# 9xVoice_MikeB_TH_v1_0a.net
KiCad netlist of a schematic drawn in EAGLE
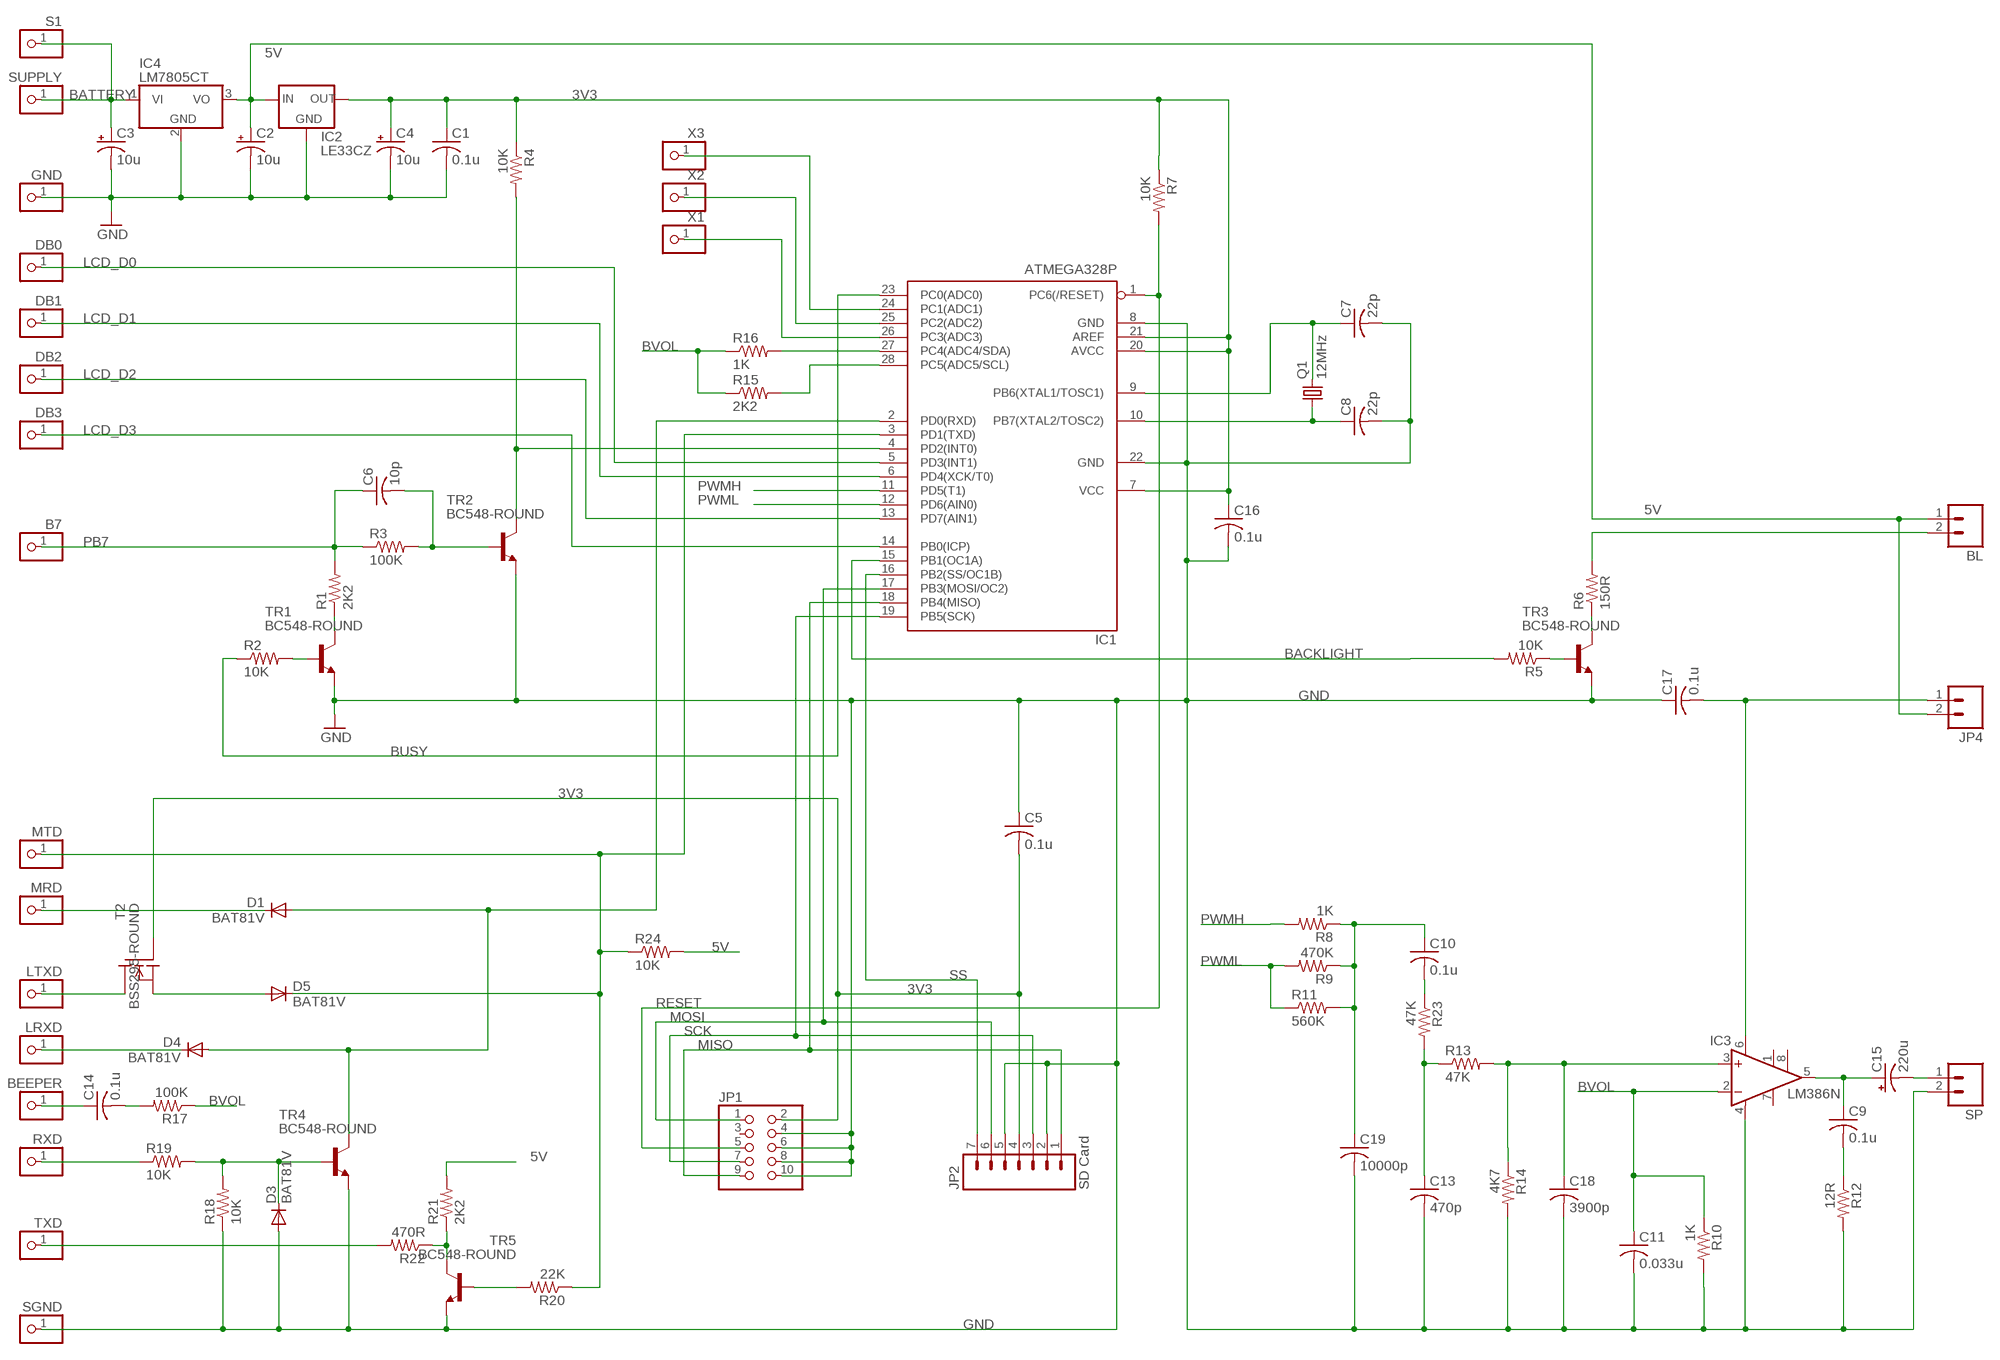
[diagram p0: schematic, sheet 1]

(export (version "E")
  (design (tool "Eeschema 10.0.6"))
  (components
    (comp (ref "B7")
      (value "PINHD-1X1")
      (footprint "eagle-import:1X01")
      (libsource (lib "eagle-import") (part "PINHD-1X1"))
    )
    (comp (ref "BEEPER")
      (value "PINHD-1X1")
      (footprint "eagle-import:1X01")
      (libsource (lib "eagle-import") (part "PINHD-1X1"))
    )
    (comp (ref "BL")
      (value "M02PTH")
      (footprint "eagle-import:1X02")
      (libsource (lib "eagle-import") (part "M02PTH"))
    )
    (comp (ref "C1")
      (value "0.1u")
      (footprint "eagle-import:C025-024X044")
      (libsource (lib "eagle-import") (part "C-US025-024X044"))
    )
    (comp (ref "C2")
      (value "10u")
      (footprint "eagle-import:E2,5-5")
      (libsource (lib "eagle-import") (part "CPOL-USE2.5-5"))
    )
    (comp (ref "C3")
      (value "10u")
      (footprint "eagle-import:E2,5-5")
      (libsource (lib "eagle-import") (part "CPOL-USE2.5-5"))
    )
    (comp (ref "C4")
      (value "10u")
      (footprint "eagle-import:E2,5-5")
      (libsource (lib "eagle-import") (part "CPOL-USE2.5-5"))
    )
    (comp (ref "C5")
      (value "0.1u")
      (footprint "eagle-import:C025-024X044")
      (libsource (lib "eagle-import") (part "C-US025-024X044"))
    )
    (comp (ref "C6")
      (value "10p")
      (footprint "eagle-import:C025-024X044")
      (libsource (lib "eagle-import") (part "C-US025-024X044"))
    )
    (comp (ref "C7")
      (value "22p")
      (footprint "eagle-import:C025-024X044")
      (libsource (lib "eagle-import") (part "C-US025-024X044"))
    )
    (comp (ref "C8")
      (value "22p")
      (footprint "eagle-import:C025-024X044")
      (libsource (lib "eagle-import") (part "C-US025-024X044"))
    )
    (comp (ref "C9")
      (value "0.1u")
      (footprint "eagle-import:C025-024X044")
      (libsource (lib "eagle-import") (part "C-US025-024X044"))
    )
    (comp (ref "C10")
      (value "0.1u")
      (footprint "eagle-import:C025-024X044")
      (libsource (lib "eagle-import") (part "C-US025-024X044"))
    )
    (comp (ref "C11")
      (value "0.033u")
      (footprint "eagle-import:C025-024X044")
      (libsource (lib "eagle-import") (part "C-US025-024X044"))
    )
    (comp (ref "C13")
      (value "470p")
      (footprint "eagle-import:C025-024X044")
      (libsource (lib "eagle-import") (part "C-US025-024X044"))
    )
    (comp (ref "C14")
      (value "0.1u")
      (footprint "eagle-import:C025-024X044")
      (libsource (lib "eagle-import") (part "C-US025-024X044"))
    )
    (comp (ref "C15")
      (value "220u")
      (footprint "eagle-import:E5-8,5")
      (libsource (lib "eagle-import") (part "CPOL-USE5-8.5"))
    )
    (comp (ref "C16")
      (value "0.1u")
      (footprint "eagle-import:C025-024X044")
      (libsource (lib "eagle-import") (part "C-US025-024X044"))
    )
    (comp (ref "C17")
      (value "0.1u")
      (footprint "eagle-import:C025-024X044")
      (libsource (lib "eagle-import") (part "C-US025-024X044"))
    )
    (comp (ref "C18")
      (value "3900p")
      (footprint "eagle-import:C025-024X044")
      (libsource (lib "eagle-import") (part "C-US025-024X044"))
    )
    (comp (ref "C19")
      (value "10000p")
      (footprint "eagle-import:C025-024X044")
      (libsource (lib "eagle-import") (part "C-US025-024X044"))
    )
    (comp (ref "D1")
      (value "BAT81V")
      (footprint "eagle-import:D-2.5")
      (libsource (lib "eagle-import") (part "DIODE-D-2.5"))
    )
    (comp (ref "D3")
      (value "BAT81V")
      (footprint "eagle-import:D-2.5")
      (libsource (lib "eagle-import") (part "DIODE-D-2.5"))
    )
    (comp (ref "D4")
      (value "BAT81V")
      (footprint "eagle-import:D-2.5")
      (libsource (lib "eagle-import") (part "DIODE-D-2.5"))
    )
    (comp (ref "D5")
      (value "BAT81V")
      (footprint "eagle-import:D-2.5")
      (libsource (lib "eagle-import") (part "DIODE-D-2.5"))
    )
    (comp (ref "DB0")
      (value "PINHD-1X1")
      (footprint "eagle-import:1X01")
      (libsource (lib "eagle-import") (part "PINHD-1X1"))
    )
    (comp (ref "DB1")
      (value "PINHD-1X1")
      (footprint "eagle-import:1X01")
      (libsource (lib "eagle-import") (part "PINHD-1X1"))
    )
    (comp (ref "DB2")
      (value "PINHD-1X1")
      (footprint "eagle-import:1X01")
      (libsource (lib "eagle-import") (part "PINHD-1X1"))
    )
    (comp (ref "DB3")
      (value "PINHD-1X1")
      (footprint "eagle-import:1X01")
      (libsource (lib "eagle-import") (part "PINHD-1X1"))
    )
    (comp (ref "GND")
      (value "PINHD-1X1")
      (footprint "eagle-import:1X01")
      (libsource (lib "eagle-import") (part "PINHD-1X1"))
    )
    (comp (ref "IC1")
      (value "ATMEGA328P")
      (footprint "eagle-import:DIL28-3-JDC")
      (libsource (lib "eagle-import") (part "MEGA8-P-JDCJDC"))
    )
    (comp (ref "IC2")
      (value "LE33CZ")
      (footprint "eagle-import:TO92-JDC")
      (libsource (lib "eagle-import") (part "78LXX-ROUND"))
    )
    (comp (ref "IC3")
      (value "LM386N")
      (footprint "eagle-import:DIL08")
      (libsource (lib "eagle-import") (part "LM386?-N1"))
    )
    (comp (ref "IC4")
      (value "LM7805CT")
      (footprint "eagle-import:TO220H")
      (libsource (lib "eagle-import") (part "78T05"))
    )
    (comp (ref "JP1")
      (value "PINHD-2X5")
      (footprint "eagle-import:2X05")
      (libsource (lib "eagle-import") (part "PINHD-2X5"))
    )
    (comp (ref "JP2")
      (value "SD Card")
      (footprint "eagle-import:1X07")
      (libsource (lib "eagle-import") (part "M07"))
    )
    (comp (ref "JP4")
      (value "M02PTH")
      (footprint "eagle-import:1X02")
      (libsource (lib "eagle-import") (part "M02PTH"))
    )
    (comp (ref "LRXD")
      (value "PINHD-1X1")
      (footprint "eagle-import:1X01")
      (libsource (lib "eagle-import") (part "PINHD-1X1"))
    )
    (comp (ref "LTXD")
      (value "PINHD-1X1")
      (footprint "eagle-import:1X01")
      (libsource (lib "eagle-import") (part "PINHD-1X1"))
    )
    (comp (ref "MRD")
      (value "PINHD-1X1")
      (footprint "eagle-import:1X01")
      (libsource (lib "eagle-import") (part "PINHD-1X1"))
    )
    (comp (ref "MTD")
      (value "PINHD-1X1")
      (footprint "eagle-import:1X01")
      (libsource (lib "eagle-import") (part "PINHD-1X1"))
    )
    (comp (ref "Q1")
      (value "12MHz")
      (footprint "eagle-import:HC49US")
      (libsource (lib "eagle-import") (part "CRYSTALHC49US"))
    )
    (comp (ref "R1")
      (value "2K2")
      (footprint "eagle-import:0207_2V")
      (libsource (lib "eagle-import") (part "R-US_0207/2V"))
    )
    (comp (ref "R2")
      (value "10K")
      (footprint "eagle-import:0204_7")
      (libsource (lib "eagle-import") (part "R-US_0204/7"))
    )
    (comp (ref "R3")
      (value "100K")
      (footprint "eagle-import:0207_2V")
      (libsource (lib "eagle-import") (part "R-US_0207/2V"))
    )
    (comp (ref "R4")
      (value "10K")
      (footprint "eagle-import:0207_2V")
      (libsource (lib "eagle-import") (part "R-US_0207/2V"))
    )
    (comp (ref "R5")
      (value "10K")
      (footprint "eagle-import:0207_2V")
      (libsource (lib "eagle-import") (part "R-US_0207/2V"))
    )
    (comp (ref "R6")
      (value "150R")
      (footprint "eagle-import:0207_2V")
      (libsource (lib "eagle-import") (part "R-US_0207/2V"))
    )
    (comp (ref "R7")
      (value "10K")
      (footprint "eagle-import:0207_2V")
      (libsource (lib "eagle-import") (part "R-US_0207/2V"))
    )
    (comp (ref "R8")
      (value "1K")
      (footprint "eagle-import:0207_2V")
      (libsource (lib "eagle-import") (part "R-US_0207/2V"))
    )
    (comp (ref "R9")
      (value "470K")
      (footprint "eagle-import:0207_2V")
      (libsource (lib "eagle-import") (part "R-US_0207/2V"))
    )
    (comp (ref "R10")
      (value "1K")
      (footprint "eagle-import:0207_2V")
      (libsource (lib "eagle-import") (part "R-US_0207/2V"))
    )
    (comp (ref "R11")
      (value "560K")
      (footprint "eagle-import:0207_2V")
      (libsource (lib "eagle-import") (part "R-US_0207/2V"))
    )
    (comp (ref "R12")
      (value "12R")
      (footprint "eagle-import:0207_2V")
      (libsource (lib "eagle-import") (part "R-US_0207/2V"))
    )
    (comp (ref "R13")
      (value "47K")
      (footprint "eagle-import:0207_2V")
      (libsource (lib "eagle-import") (part "R-US_0207/2V"))
    )
    (comp (ref "R14")
      (value "4K7")
      (footprint "eagle-import:0207_2V")
      (libsource (lib "eagle-import") (part "R-US_0207/2V"))
    )
    (comp (ref "R15")
      (value "2K2")
      (footprint "eagle-import:0207_2V")
      (libsource (lib "eagle-import") (part "R-US_0207/2V"))
    )
    (comp (ref "R16")
      (value "1K")
      (footprint "eagle-import:0207_2V")
      (libsource (lib "eagle-import") (part "R-US_0207/2V"))
    )
    (comp (ref "R17")
      (value "100K")
      (footprint "eagle-import:0207_2V")
      (libsource (lib "eagle-import") (part "R-US_0207/2V"))
    )
    (comp (ref "R18")
      (value "10K")
      (footprint "eagle-import:0207_2V")
      (libsource (lib "eagle-import") (part "R-US_0207/2V"))
    )
    (comp (ref "R19")
      (value "10K")
      (footprint "eagle-import:0207_2V")
      (libsource (lib "eagle-import") (part "R-US_0207/2V"))
    )
    (comp (ref "R20")
      (value "22K")
      (footprint "eagle-import:0207_2V")
      (libsource (lib "eagle-import") (part "R-US_0207/2V"))
    )
    (comp (ref "R21")
      (value "2K2")
      (footprint "eagle-import:0207_2V")
      (libsource (lib "eagle-import") (part "R-US_0207/2V"))
    )
    (comp (ref "R22")
      (value "470R")
      (footprint "eagle-import:0207_2V")
      (libsource (lib "eagle-import") (part "R-US_0207/2V"))
    )
    (comp (ref "R23")
      (value "47K")
      (footprint "eagle-import:0207_2V")
      (libsource (lib "eagle-import") (part "R-US_0207/2V"))
    )
    (comp (ref "R24")
      (value "10K")
      (footprint "eagle-import:0207_2V")
      (libsource (lib "eagle-import") (part "R-US_0207/2V"))
    )
    (comp (ref "RXD")
      (value "PINHD-1X1")
      (footprint "eagle-import:1X01")
      (libsource (lib "eagle-import") (part "PINHD-1X1"))
    )
    (comp (ref "S1")
      (value "PINHD-1X1")
      (footprint "eagle-import:1X01")
      (libsource (lib "eagle-import") (part "PINHD-1X1"))
    )
    (comp (ref "SGND")
      (value "PINHD-1X1")
      (footprint "eagle-import:1X01")
      (libsource (lib "eagle-import") (part "PINHD-1X1"))
    )
    (comp (ref "SP")
      (value "M02PTH")
      (footprint "eagle-import:1X02")
      (libsource (lib "eagle-import") (part "M02PTH"))
    )
    (comp (ref "SUPPLY")
      (value "PINHD-1X1")
      (footprint "eagle-import:1X01")
      (libsource (lib "eagle-import") (part "PINHD-1X1"))
    )
    (comp (ref "T2")
      (value "BSS295-ROUND")
      (footprint "eagle-import:TO92-JDC")
      (libsource (lib "eagle-import") (part "BSS295-ROUND"))
    )
    (comp (ref "TR1")
      (value "BC548-ROUND")
      (footprint "eagle-import:TO92-JDC")
      (libsource (lib "eagle-import") (part "BC548-ROUND"))
    )
    (comp (ref "TR2")
      (value "BC548-ROUND")
      (footprint "eagle-import:TO92-JDC")
      (libsource (lib "eagle-import") (part "BC548-ROUND"))
    )
    (comp (ref "TR3")
      (value "BC548-ROUND")
      (footprint "eagle-import:TO92-JDC")
      (libsource (lib "eagle-import") (part "BC548-ROUND"))
    )
    (comp (ref "TR4")
      (value "BC548-ROUND")
      (footprint "eagle-import:TO92-JDC")
      (libsource (lib "eagle-import") (part "BC548-ROUND"))
    )
    (comp (ref "TR5")
      (value "BC548-ROUND")
      (footprint "eagle-import:TO92-JDC")
      (libsource (lib "eagle-import") (part "BC548-ROUND"))
    )
    (comp (ref "TXD")
      (value "PINHD-1X1")
      (footprint "eagle-import:1X01")
      (libsource (lib "eagle-import") (part "PINHD-1X1"))
    )
    (comp (ref "X1")
      (value "PINHD-1X1")
      (footprint "eagle-import:1X01")
      (libsource (lib "eagle-import") (part "PINHD-1X1"))
    )
    (comp (ref "X2")
      (value "PINHD-1X1")
      (footprint "eagle-import:1X01")
      (libsource (lib "eagle-import") (part "PINHD-1X1"))
    )
    (comp (ref "X3")
      (value "PINHD-1X1")
      (footprint "eagle-import:1X01")
      (libsource (lib "eagle-import") (part "PINHD-1X1"))
    )
  )
  (nets
    (net (code "1") (name "/3V3") (class "Default")
      (node (ref "C1") (pin "1") (pinfunction "1_1") (pintype "passive"))
      (node (ref "C16") (pin "1") (pinfunction "1_1") (pintype "passive"))
      (node (ref "C4") (pin "+") (pinfunction "+_+") (pintype "passive"))
      (node (ref "C5") (pin "2") (pinfunction "2_2") (pintype "passive"))
      (node (ref "IC1") (pin "20") (pinfunction "AVCC_20") (pintype "power_in"))
      (node (ref "IC1") (pin "21") (pinfunction "AREF_21") (pintype "passive"))
      (node (ref "IC1") (pin "7") (pinfunction "VCC_7") (pintype "power_in"))
      (node (ref "IC2") (pin "C") (pinfunction "OUT_C") (pintype "passive"))
      (node (ref "JP1") (pin "2") (pinfunction "2_2") (pintype "passive"))
      (node (ref "JP2") (pin "4") (pinfunction "4_4") (pintype "passive"))
      (node (ref "R4") (pin "1") (pinfunction "1_1") (pintype "passive"))
      (node (ref "R7") (pin "1") (pinfunction "1_1") (pintype "passive"))
      (node (ref "T2") (pin "B") (pinfunction "G_B") (pintype "passive"))
    )
    (net (code "2") (name "/5V") (class "Default")
      (node (ref "BL") (pin "1") (pinfunction "1_1") (pintype "passive"))
      (node (ref "C2") (pin "+") (pinfunction "+_+") (pintype "passive"))
      (node (ref "IC2") (pin "E") (pinfunction "IN_E") (pintype "input"))
      (node (ref "IC4") (pin "3") (pinfunction "VO_3") (pintype "passive"))
      (node (ref "JP4") (pin "2") (pinfunction "2_2") (pintype "passive"))
      (node (ref "R21") (pin "2") (pinfunction "2_2") (pintype "passive"))
      (node (ref "R24") (pin "2") (pinfunction "2_2") (pintype "passive"))
    )
    (net (code "3") (name "/BACKLIGHT") (class "Default")
      (node (ref "IC1") (pin "15") (pinfunction "PB1(OC1A)_15") (pintype "bidirectional"))
      (node (ref "R5") (pin "2") (pinfunction "2_2") (pintype "passive"))
    )
    (net (code "4") (name "/BATTERY") (class "Default")
      (node (ref "C3") (pin "+") (pinfunction "+_+") (pintype "passive"))
      (node (ref "IC4") (pin "1") (pinfunction "VI_1") (pintype "input"))
      (node (ref "S1") (pin "1") (pinfunction "1_1") (pintype "passive"))
      (node (ref "SUPPLY") (pin "1") (pinfunction "1_1") (pintype "passive"))
    )
    (net (code "5") (name "/BUSY") (class "Default")
      (node (ref "IC1") (pin "23") (pinfunction "PC0(ADC0)_23") (pintype "bidirectional"))
      (node (ref "R2") (pin "1") (pinfunction "1_1") (pintype "passive"))
    )
    (net (code "6") (name "/BVOL") (class "Default")
      (node (ref "C11") (pin "1") (pinfunction "1_1") (pintype "passive"))
      (node (ref "IC3") (pin "2") (pinfunction "-IN_2") (pintype "input"))
      (node (ref "R10") (pin "1") (pinfunction "1_1") (pintype "passive"))
      (node (ref "R15") (pin "1") (pinfunction "1_1") (pintype "passive"))
      (node (ref "R16") (pin "1") (pinfunction "1_1") (pintype "passive"))
      (node (ref "R17") (pin "1") (pinfunction "1_1") (pintype "passive"))
    )
    (net (code "7") (name "/LCD_D0") (class "Default")
      (node (ref "DB0") (pin "1") (pinfunction "1_1") (pintype "passive"))
      (node (ref "IC1") (pin "5") (pinfunction "PD3(INT1)_5") (pintype "bidirectional"))
    )
    (net (code "8") (name "/LCD_D1") (class "Default")
      (node (ref "DB1") (pin "1") (pinfunction "1_1") (pintype "passive"))
      (node (ref "IC1") (pin "6") (pinfunction "PD4(XCK/T0)_6") (pintype "bidirectional"))
    )
    (net (code "9") (name "/LCD_D2") (class "Default")
      (node (ref "DB2") (pin "1") (pinfunction "1_1") (pintype "passive"))
      (node (ref "IC1") (pin "13") (pinfunction "PD7(AIN1)_13") (pintype "bidirectional"))
    )
    (net (code "10") (name "/LCD_D3") (class "Default")
      (node (ref "DB3") (pin "1") (pinfunction "1_1") (pintype "passive"))
      (node (ref "IC1") (pin "14") (pinfunction "PB0(ICP)_14") (pintype "bidirectional"))
    )
    (net (code "11") (name "/MISO") (class "Default")
      (node (ref "IC1") (pin "18") (pinfunction "PB4(MISO)_18") (pintype "bidirectional"))
      (node (ref "JP1") (pin "9") (pinfunction "9_9") (pintype "passive"))
      (node (ref "JP2") (pin "1") (pinfunction "1_1") (pintype "passive"))
    )
    (net (code "12") (name "/MOSI") (class "Default")
      (node (ref "IC1") (pin "17") (pinfunction "PB3(MOSI/OC2)_17") (pintype "bidirectional"))
      (node (ref "JP1") (pin "1") (pinfunction "1_1") (pintype "passive"))
      (node (ref "JP2") (pin "6") (pinfunction "6_6") (pintype "passive"))
    )
    (net (code "13") (name "/PB7") (class "Default")
      (node (ref "B7") (pin "1") (pinfunction "1_1") (pintype "passive"))
      (node (ref "C6") (pin "1") (pinfunction "1_1") (pintype "passive"))
      (node (ref "R1") (pin "2") (pinfunction "2_2") (pintype "passive"))
      (node (ref "R3") (pin "1") (pinfunction "1_1") (pintype "passive"))
    )
    (net (code "14") (name "/PWMH") (class "Default")
      (node (ref "IC1") (pin "11") (pinfunction "PD5(T1)_11") (pintype "bidirectional"))
      (node (ref "R8") (pin "2") (pinfunction "2_2") (pintype "passive"))
    )
    (net (code "15") (name "/PWML") (class "Default")
      (node (ref "IC1") (pin "12") (pinfunction "PD6(AIN0)_12") (pintype "bidirectional"))
      (node (ref "R11") (pin "1") (pinfunction "1_1") (pintype "passive"))
      (node (ref "R9") (pin "2") (pinfunction "2_2") (pintype "passive"))
    )
    (net (code "16") (name "/RESET") (class "Default")
      (node (ref "IC1") (pin "1") (pinfunction "PC6(/RESET)_1") (pintype "bidirectional"))
      (node (ref "JP1") (pin "5") (pinfunction "5_5") (pintype "passive"))
      (node (ref "R7") (pin "2") (pinfunction "2_2") (pintype "passive"))
    )
    (net (code "17") (name "/SCK") (class "Default")
      (node (ref "IC1") (pin "19") (pinfunction "PB5(SCK)_19") (pintype "bidirectional"))
      (node (ref "JP1") (pin "7") (pinfunction "7_7") (pintype "passive"))
      (node (ref "JP2") (pin "3") (pinfunction "3_3") (pintype "passive"))
    )
    (net (code "18") (name "/SS") (class "Default")
      (node (ref "IC1") (pin "16") (pinfunction "PB2(SS/OC1B)_16") (pintype "bidirectional"))
      (node (ref "JP2") (pin "7") (pinfunction "7_7") (pintype "passive"))
    )
    (net (code "19") (name "GND") (class "Default")
      (node (ref "C1") (pin "2") (pinfunction "2_2") (pintype "passive"))
      (node (ref "C11") (pin "2") (pinfunction "2_2") (pintype "passive"))
      (node (ref "C13") (pin "2") (pinfunction "2_2") (pintype "passive"))
      (node (ref "C16") (pin "2") (pinfunction "2_2") (pintype "passive"))
      (node (ref "C17") (pin "1") (pinfunction "1_1") (pintype "passive"))
      (node (ref "C18") (pin "2") (pinfunction "2_2") (pintype "passive"))
      (node (ref "C19") (pin "2") (pinfunction "2_2") (pintype "passive"))
      (node (ref "C2") (pin "-") (pinfunction "-_-") (pintype "passive"))
      (node (ref "C3") (pin "-") (pinfunction "-_-") (pintype "passive"))
      (node (ref "C4") (pin "-") (pinfunction "-_-") (pintype "passive"))
      (node (ref "C5") (pin "1") (pinfunction "1_1") (pintype "passive"))
      (node (ref "C7") (pin "2") (pinfunction "2_2") (pintype "passive"))
      (node (ref "C8") (pin "2") (pinfunction "2_2") (pintype "passive"))
      (node (ref "D3") (pin "A") (pinfunction "A_A") (pintype "passive"))
      (node (ref "GND") (pin "1") (pinfunction "1_1") (pintype "passive"))
      (node (ref "IC1") (pin "22") (pinfunction "GND_22") (pintype "power_in"))
      (node (ref "IC1") (pin "8") (pinfunction "GND_8") (pintype "power_in"))
      (node (ref "IC2") (pin "B") (pinfunction "GND_B") (pintype "input"))
      (node (ref "IC3") (pin "4") (pinfunction "GND_4") (pintype "power_in"))
      (node (ref "IC4") (pin "2") (pinfunction "GND_2") (pintype "passive"))
      (node (ref "JP1") (pin "10") (pinfunction "10_10") (pintype "passive"))
      (node (ref "JP1") (pin "4") (pinfunction "4_4") (pintype "passive"))
      (node (ref "JP1") (pin "6") (pinfunction "6_6") (pintype "passive"))
      (node (ref "JP1") (pin "8") (pinfunction "8_8") (pintype "passive"))
      (node (ref "JP2") (pin "2") (pinfunction "2_2") (pintype "passive"))
      (node (ref "JP2") (pin "5") (pinfunction "5_5") (pintype "passive"))
      (node (ref "R10") (pin "2") (pinfunction "2_2") (pintype "passive"))
      (node (ref "R12") (pin "2") (pinfunction "2_2") (pintype "passive"))
      (node (ref "R14") (pin "2") (pinfunction "2_2") (pintype "passive"))
      (node (ref "R18") (pin "1") (pinfunction "1_1") (pintype "passive"))
      (node (ref "SGND") (pin "1") (pinfunction "1_1") (pintype "passive"))
      (node (ref "SP") (pin "2") (pinfunction "2_2") (pintype "passive"))
      (node (ref "TR1") (pin "E") (pinfunction "E_E") (pintype "passive"))
      (node (ref "TR2") (pin "E") (pinfunction "E_E") (pintype "passive"))
      (node (ref "TR3") (pin "E") (pinfunction "E_E") (pintype "passive"))
      (node (ref "TR4") (pin "E") (pinfunction "E_E") (pintype "passive"))
      (node (ref "TR5") (pin "E") (pinfunction "E_E") (pintype "passive"))
    )
    (net (code "20") (name "Net-(BEEPER-Pad1)") (class "Default")
      (node (ref "BEEPER") (pin "1") (pinfunction "1_1") (pintype "passive"))
      (node (ref "C14") (pin "1") (pinfunction "1_1") (pintype "passive"))
    )
    (net (code "21") (name "Net-(BL-Pad2)") (class "Default")
      (node (ref "BL") (pin "2") (pinfunction "2_2") (pintype "passive"))
      (node (ref "R6") (pin "2") (pinfunction "2_2") (pintype "passive"))
    )
    (net (code "22") (name "Net-(C6-Pad2)") (class "Default")
      (node (ref "C6") (pin "2") (pinfunction "2_2") (pintype "passive"))
      (node (ref "R3") (pin "2") (pinfunction "2_2") (pintype "passive"))
      (node (ref "TR2") (pin "B") (pinfunction "B_B") (pintype "passive"))
    )
    (net (code "23") (name "Net-(C9-Pad2)") (class "Default")
      (node (ref "C9") (pin "2") (pinfunction "2_2") (pintype "passive"))
      (node (ref "R12") (pin "1") (pinfunction "1_1") (pintype "passive"))
    )
    (net (code "24") (name "Net-(C10-Pad1)") (class "Default")
      (node (ref "C10") (pin "1") (pinfunction "1_1") (pintype "passive"))
      (node (ref "C19") (pin "1") (pinfunction "1_1") (pintype "passive"))
      (node (ref "R11") (pin "2") (pinfunction "2_2") (pintype "passive"))
      (node (ref "R8") (pin "1") (pinfunction "1_1") (pintype "passive"))
      (node (ref "R9") (pin "1") (pinfunction "1_1") (pintype "passive"))
    )
    (net (code "25") (name "Net-(C10-Pad2)") (class "Default")
      (node (ref "C10") (pin "2") (pinfunction "2_2") (pintype "passive"))
      (node (ref "R23") (pin "1") (pinfunction "1_1") (pintype "passive"))
    )
    (net (code "26") (name "Net-(C13-Pad1)") (class "Default")
      (node (ref "C13") (pin "1") (pinfunction "1_1") (pintype "passive"))
      (node (ref "R13") (pin "1") (pinfunction "1_1") (pintype "passive"))
      (node (ref "R23") (pin "2") (pinfunction "2_2") (pintype "passive"))
    )
    (net (code "27") (name "Net-(C14-Pad2)") (class "Default")
      (node (ref "C14") (pin "2") (pinfunction "2_2") (pintype "passive"))
      (node (ref "R17") (pin "2") (pinfunction "2_2") (pintype "passive"))
    )
    (net (code "28") (name "Net-(C15-Pad-)") (class "Default")
      (node (ref "C15") (pin "-") (pinfunction "-_-") (pintype "passive"))
      (node (ref "SP") (pin "1") (pinfunction "1_1") (pintype "passive"))
    )
    (net (code "29") (name "Net-(D1-PadC)") (class "Default")
      (node (ref "D1") (pin "C") (pinfunction "C_C") (pintype "passive"))
      (node (ref "MRD") (pin "1") (pinfunction "1_1") (pintype "passive"))
    )
    (net (code "30") (name "Net-(D3-PadC)") (class "Default")
      (node (ref "D3") (pin "C") (pinfunction "C_C") (pintype "passive"))
      (node (ref "R18") (pin "2") (pinfunction "2_2") (pintype "passive"))
      (node (ref "R19") (pin "2") (pinfunction "2_2") (pintype "passive"))
      (node (ref "TR4") (pin "B") (pinfunction "B_B") (pintype "passive"))
    )
    (net (code "31") (name "Net-(D4-PadC)") (class "Default")
      (node (ref "D4") (pin "C") (pinfunction "C_C") (pintype "passive"))
      (node (ref "LRXD") (pin "1") (pinfunction "1_1") (pintype "passive"))
    )
    (net (code "32") (name "Net-(IC1-PB6(XTAL1{slash}TOSC1))") (class "Default")
      (node (ref "C7") (pin "1") (pinfunction "1_1") (pintype "passive"))
      (node (ref "IC1") (pin "9") (pinfunction "PB6(XTAL1/TOSC1)_9") (pintype "bidirectional"))
      (node (ref "Q1") (pin "2") (pinfunction "2_2") (pintype "passive"))
    )
    (net (code "33") (name "Net-(IC1-PB7(XTAL2{slash}TOSC2))") (class "Default")
      (node (ref "C8") (pin "1") (pinfunction "1_1") (pintype "passive"))
      (node (ref "IC1") (pin "10") (pinfunction "PB7(XTAL2/TOSC2)_10") (pintype "bidirectional"))
      (node (ref "Q1") (pin "1") (pinfunction "1_1") (pintype "passive"))
    )
    (net (code "34") (name "Net-(IC1-PC1(ADC1))") (class "Default")
      (node (ref "IC1") (pin "24") (pinfunction "PC1(ADC1)_24") (pintype "bidirectional"))
      (node (ref "X3") (pin "1") (pinfunction "1_1") (pintype "passive"))
    )
    (net (code "35") (name "Net-(IC1-PC2(ADC2))") (class "Default")
      (node (ref "IC1") (pin "25") (pinfunction "PC2(ADC2)_25") (pintype "bidirectional"))
      (node (ref "X2") (pin "1") (pinfunction "1_1") (pintype "passive"))
    )
    (net (code "36") (name "Net-(IC1-PC3(ADC3))") (class "Default")
      (node (ref "IC1") (pin "26") (pinfunction "PC3(ADC3)_26") (pintype "bidirectional"))
      (node (ref "X1") (pin "1") (pinfunction "1_1") (pintype "passive"))
    )
    (net (code "37") (name "Net-(IC1-PC4(ADC4{slash}SDA))") (class "Default")
      (node (ref "IC1") (pin "27") (pinfunction "PC4(ADC4/SDA)_27") (pintype "bidirectional"))
      (node (ref "R16") (pin "2") (pinfunction "2_2") (pintype "passive"))
    )
    (net (code "38") (name "Net-(IC1-PC5(ADC5{slash}SCL))") (class "Default")
      (node (ref "IC1") (pin "28") (pinfunction "PC5(ADC5/SCL)_28") (pintype "bidirectional"))
      (node (ref "R15") (pin "2") (pinfunction "2_2") (pintype "passive"))
    )
    (net (code "39") (name "Net-(IC1-PD0(RXD))") (class "Default")
      (node (ref "D1") (pin "A") (pinfunction "A_A") (pintype "passive"))
      (node (ref "D4") (pin "A") (pinfunction "A_A") (pintype "passive"))
      (node (ref "IC1") (pin "2") (pinfunction "PD0(RXD)_2") (pintype "bidirectional"))
      (node (ref "TR4") (pin "C") (pinfunction "C_C") (pintype "passive"))
    )
    (net (code "40") (name "Net-(IC1-PD1(TXD))") (class "Default")
      (node (ref "D5") (pin "C") (pinfunction "C_C") (pintype "passive"))
      (node (ref "IC1") (pin "3") (pinfunction "PD1(TXD)_3") (pintype "bidirectional"))
      (node (ref "MTD") (pin "1") (pinfunction "1_1") (pintype "passive"))
      (node (ref "R20") (pin "1") (pinfunction "1_1") (pintype "passive"))
      (node (ref "R24") (pin "1") (pinfunction "1_1") (pintype "passive"))
    )
    (net (code "41") (name "Net-(IC1-PD2(INT0))") (class "Default")
      (node (ref "IC1") (pin "4") (pinfunction "PD2(INT0)_4") (pintype "bidirectional"))
      (node (ref "R4") (pin "2") (pinfunction "2_2") (pintype "passive"))
      (node (ref "TR2") (pin "C") (pinfunction "C_C") (pintype "passive"))
    )
    (net (code "42") (name "Net-(IC3-+IN)") (class "Default")
      (node (ref "C18") (pin "1") (pinfunction "1_1") (pintype "passive"))
      (node (ref "IC3") (pin "3") (pinfunction "+IN_3") (pintype "input"))
      (node (ref "R13") (pin "2") (pinfunction "2_2") (pintype "passive"))
      (node (ref "R14") (pin "1") (pinfunction "1_1") (pintype "passive"))
    )
    (net (code "43") (name "Net-(IC3-OUT)") (class "Default")
      (node (ref "C15") (pin "+") (pinfunction "+_+") (pintype "passive"))
      (node (ref "C9") (pin "1") (pinfunction "1_1") (pintype "passive"))
      (node (ref "IC3") (pin "5") (pinfunction "OUT_5") (pintype "output"))
    )
    (net (code "44") (name "Net-(IC3-VS)") (class "Default")
      (node (ref "C17") (pin "2") (pinfunction "2_2") (pintype "passive"))
      (node (ref "IC3") (pin "6") (pinfunction "VS_6") (pintype "power_in"))
      (node (ref "JP4") (pin "1") (pinfunction "1_1") (pintype "passive"))
    )
    (net (code "45") (name "Net-(R1-Pad1)") (class "Default")
      (node (ref "R1") (pin "1") (pinfunction "1_1") (pintype "passive"))
      (node (ref "TR1") (pin "C") (pinfunction "C_C") (pintype "passive"))
    )
    (net (code "46") (name "Net-(R2-Pad2)") (class "Default")
      (node (ref "R2") (pin "2") (pinfunction "2_2") (pintype "passive"))
      (node (ref "TR1") (pin "B") (pinfunction "B_B") (pintype "passive"))
    )
    (net (code "47") (name "Net-(R5-Pad1)") (class "Default")
      (node (ref "R5") (pin "1") (pinfunction "1_1") (pintype "passive"))
      (node (ref "TR3") (pin "B") (pinfunction "B_B") (pintype "passive"))
    )
    (net (code "48") (name "Net-(R6-Pad1)") (class "Default")
      (node (ref "R6") (pin "1") (pinfunction "1_1") (pintype "passive"))
      (node (ref "TR3") (pin "C") (pinfunction "C_C") (pintype "passive"))
    )
    (net (code "49") (name "Net-(R19-Pad1)") (class "Default")
      (node (ref "R19") (pin "1") (pinfunction "1_1") (pintype "passive"))
      (node (ref "RXD") (pin "1") (pinfunction "1_1") (pintype "passive"))
    )
    (net (code "50") (name "Net-(R20-Pad2)") (class "Default")
      (node (ref "R20") (pin "2") (pinfunction "2_2") (pintype "passive"))
      (node (ref "TR5") (pin "B") (pinfunction "B_B") (pintype "passive"))
    )
    (net (code "51") (name "Net-(R21-Pad1)") (class "Default")
      (node (ref "R21") (pin "1") (pinfunction "1_1") (pintype "passive"))
      (node (ref "R22") (pin "1") (pinfunction "1_1") (pintype "passive"))
      (node (ref "TR5") (pin "C") (pinfunction "C_C") (pintype "passive"))
    )
    (net (code "52") (name "Net-(R22-Pad2)") (class "Default")
      (node (ref "R22") (pin "2") (pinfunction "2_2") (pintype "passive"))
      (node (ref "TXD") (pin "1") (pinfunction "1_1") (pintype "passive"))
    )
    (net (code "53") (name "Net-(T2-D)") (class "Default")
      (node (ref "LTXD") (pin "1") (pinfunction "1_1") (pintype "passive"))
      (node (ref "T2") (pin "E") (pinfunction "D_E") (pintype "passive"))
    )
    (net (code "54") (name "Net-(T2-S)") (class "Default")
      (node (ref "D5") (pin "A") (pinfunction "A_A") (pintype "passive"))
      (node (ref "T2") (pin "C") (pinfunction "S_C") (pintype "passive"))
    )
    (net (code "55") (name "unconnected-(IC3-BYPASS-Pad7)") (class "Default")
      (node (ref "IC3") (pin "7") (pinfunction "BYPASS_7") (pintype "passive"))
    )
    (net (code "56") (name "unconnected-(IC3-GAIN-Pad1)") (class "Default")
      (node (ref "IC3") (pin "1") (pinfunction "GAIN_1") (pintype "passive"))
    )
    (net (code "57") (name "unconnected-(IC3-GAIN-Pad8)") (class "Default")
      (node (ref "IC3") (pin "8") (pinfunction "GAIN_8") (pintype "passive"))
    )
    (net (code "58") (name "unconnected-(JP1-Pad3)") (class "Default")
      (node (ref "JP1") (pin "3") (pinfunction "3_3") (pintype "passive"))
    )
  )
)
